# MercurialSDR_PWR.net
KiCad netlist of a schematic drawn in Altium Designer
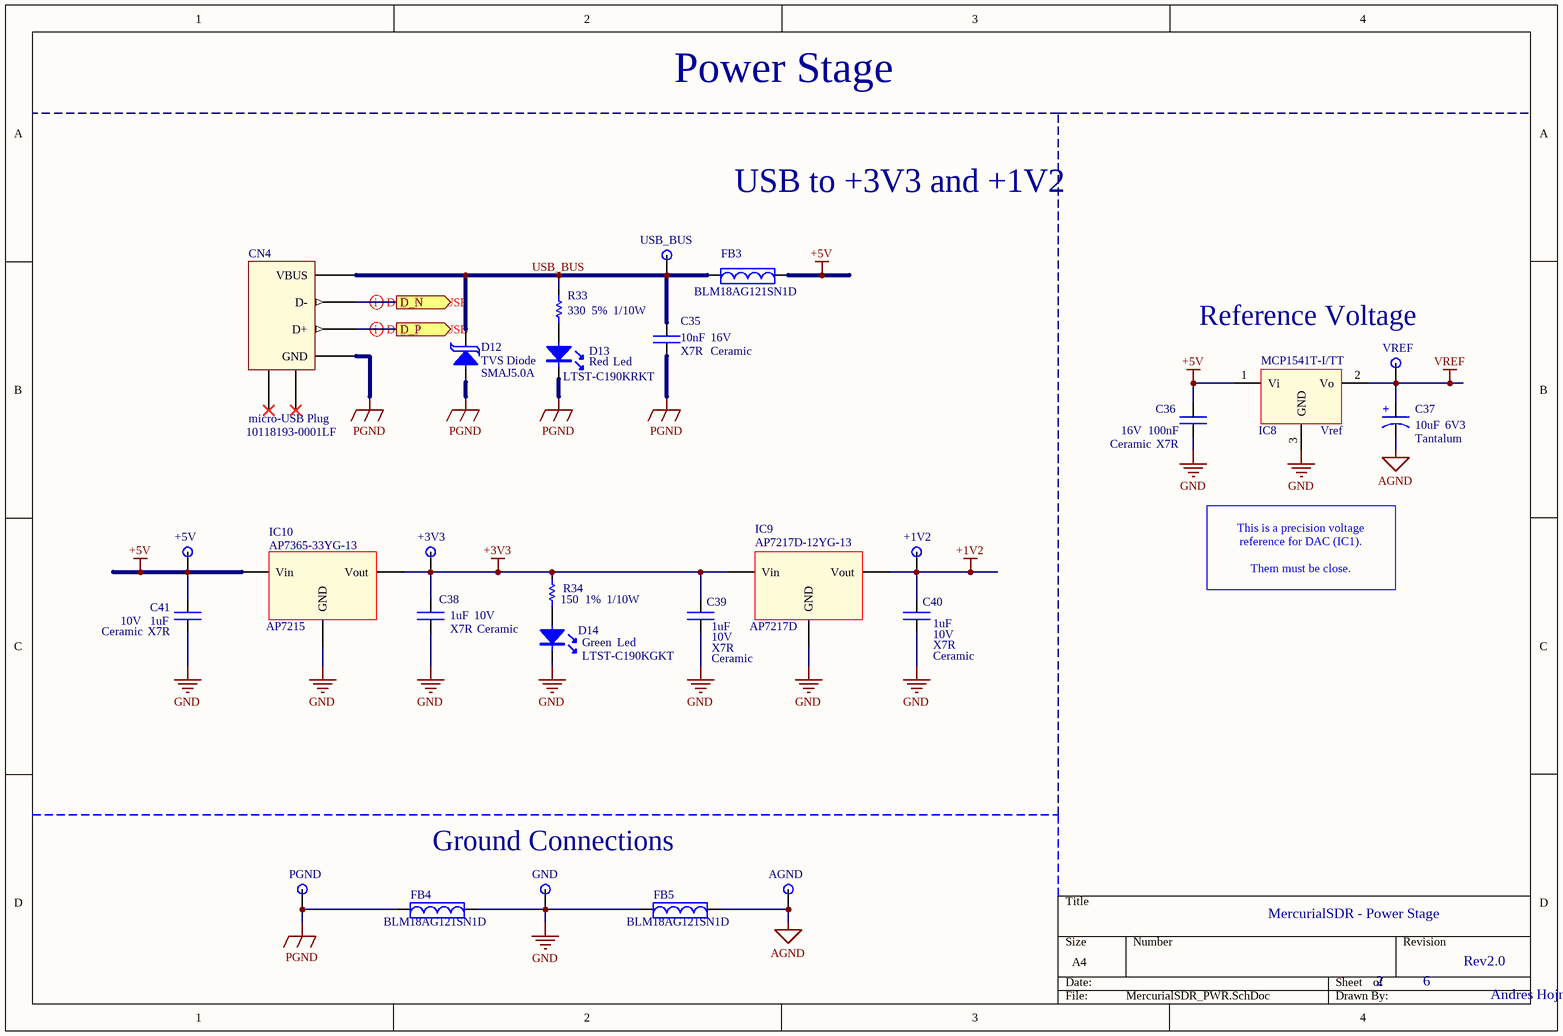
[diagram p0: MercurialSDR_PWR.SchDoc]

(export (version "E")
  (design (tool "Eeschema 10.0.6"))
  (components
    (comp (ref "C35")
      (value "10nF")
      (footprint "CAP_0603")
      (description "Capacitor no polarizado")
      (fields
        (field (name "TEMP COEF") "X7R")
        (field (name "PART NUMBER") "CC0603KRX7R7BB103")
        (field (name "VR") "16V")
        (field (name "MATERIAL") "Ceramic")
        (field (name "Comment") "Capacitor")
      )
      (libsource (lib "MercurialSDR") (part "Cap"))
    )
    (comp (ref "C36")
      (value "100nF")
      (footprint "CAP_0603")
      (description "Capacitor no polarizado")
      (fields
        (field (name "TEMP COEF") "X7R")
        (field (name "PART NUMBER") "CL10B104KO8NNNC")
        (field (name "VR") "16V")
        (field (name "MATERIAL") "Ceramic")
        (field (name "Comment") "Capacitor")
      )
      (libsource (lib "MercurialSDR") (part "Cap"))
    )
    (comp (ref "C37")
      (value "10uF")
      (footprint "CAP_TANT_1206")
      (description "Capacitor polarizado")
      (fields
        (field (name "PART NUMBER") "TAJA106K006RNJ")
        (field (name "VR") "6V3")
        (field (name "MATERIAL") "Tantalum")
        (field (name "Comment") "Capacitor Polarizado")
      )
      (libsource (lib "MercurialSDR") (part "Cap Pol"))
    )
    (comp (ref "C38")
      (value "1uF")
      (footprint "CAP_0603")
      (description "Capacitor no polarizado")
      (fields
        (field (name "TEMP COEF") "X7R")
        (field (name "PART NUMBER") "CL10B105KP8NNNC")
        (field (name "VR") "10V")
        (field (name "MATERIAL") "Ceramic")
        (field (name "Comment") "Capacitor")
      )
      (libsource (lib "MercurialSDR") (part "Cap"))
    )
    (comp (ref "C39")
      (value "1uF")
      (footprint "CAP_0603")
      (description "Capacitor no polarizado")
      (fields
        (field (name "TEMP COEF") "X7R")
        (field (name "PART NUMBER") "CL10B105KP8NNNC")
        (field (name "VR") "10V")
        (field (name "MATERIAL") "Ceramic")
        (field (name "Comment") "Capacitor")
      )
      (libsource (lib "MercurialSDR") (part "Cap"))
    )
    (comp (ref "C40")
      (value "1uF")
      (footprint "CAP_0603")
      (description "Capacitor no polarizado")
      (fields
        (field (name "TEMP COEF") "X7R")
        (field (name "PART NUMBER") "CL10B105KP8NNNC")
        (field (name "VR") "10V")
        (field (name "MATERIAL") "Ceramic")
        (field (name "Comment") "Capacitor")
      )
      (libsource (lib "MercurialSDR") (part "Cap"))
    )
    (comp (ref "C41")
      (value "1uF")
      (footprint "CAP_0603")
      (description "Capacitor no polarizado")
      (fields
        (field (name "TEMP COEF") "X7R")
        (field (name "PART NUMBER") "CL10B105KP8NNNC")
        (field (name "VR") "10V")
        (field (name "MATERIAL") "Ceramic")
        (field (name "Comment") "Capacitor")
      )
      (libsource (lib "MercurialSDR") (part "Cap"))
    )
    (comp (ref "CN4")
      (value "micro-USB Plug")
      (footprint "USB_Micro")
      (description "USB Plug")
      (fields (field (name "PART NUMBER") "10118193-0001LF"))
      (libsource (lib "MercurialSDR") (part "USB Plug"))
    )
    (comp (ref "D12")
      (value "TVS Diode")
      (footprint "DO-214AC")
      (description "TVS (Supresor de transitorios)")
      (fields (field (name "PART NUMBER") "SMAJ5.0A"))
      (libsource (lib "MercurialSDR") (part "TVS_DIODE"))
    )
    (comp (ref "D13")
      (value "Led")
      (footprint "LED_0603")
      (fields (field (name "COLOR") "Red") (field (name "PART NUMBER") "LTST-C190KRKT"))
      (libsource (lib "MercurialSDR") (part "Led"))
    )
    (comp (ref "D14")
      (value "Led")
      (footprint "LED_0603")
      (fields (field (name "COLOR") "Green") (field (name "PART NUMBER") "LTST-C190KGKT"))
      (libsource (lib "MercurialSDR") (part "Led"))
    )
    (comp (ref "FB3")
      (value "Ferrite Bead")
      (footprint "FERRITE_BEAD_0603")
      (fields (field (name "PART NUMBER") "BLM18AG121SN1D"))
      (libsource (lib "MercurialSDR") (part "Ferrite Bead"))
    )
    (comp (ref "FB4")
      (value "Ferrite Bead")
      (footprint "FERRITE_BEAD_0603")
      (fields (field (name "PART NUMBER") "BLM18AG121SN1D"))
      (libsource (lib "MercurialSDR") (part "Ferrite Bead"))
    )
    (comp (ref "FB5")
      (value "Ferrite Bead")
      (footprint "FERRITE_BEAD_0603")
      (fields (field (name "PART NUMBER") "BLM18AG121SN1D"))
      (libsource (lib "MercurialSDR") (part "Ferrite Bead"))
    )
    (comp (ref "IC8")
      (value "Vref")
      (footprint "SOT-23-3")
      (description "Reference Voltage")
      (fields (field (name "PART NUMBER") "MCP1541T-I/TT"))
      (libsource (lib "MercurialSDR") (part "MCP1541"))
    )
    (comp (ref "IC9")
      (value "AP7217D")
      (footprint "SOT89-3L")
      (description "Linear Voltage Regulator 1V2")
      (fields (field (name "PART NUMBER") "AP7217D-12YG-13"))
      (libsource (lib "MercurialSDR") (part "AP7217D"))
    )
    (comp (ref "IC10")
      (value "AP7215")
      (footprint "SOT89-3L")
      (description "Linear Voltage Regulator 3v3")
      (fields (field (name "PART NUMBER") "AP7365-33YG-13"))
      (libsource (lib "MercurialSDR") (part "AP7215"))
    )
    (comp (ref "R33")
      (value "330")
      (footprint "RES_0603")
      (description "Resistor")
      (fields
        (field (name "POWER") "1/10W")
        (field (name "PART NUMBER") "CR0603-JW-331ELF")
        (field (name "TOLERANCE") "5%")
        (field (name "Comment") "Resistor SMD")
      )
      (libsource (lib "MercurialSDR") (part "Res"))
    )
    (comp (ref "R34")
      (value "150")
      (footprint "RES_0603")
      (description "Resistor")
      (fields
        (field (name "POWER") "1/10W")
        (field (name "PART NUMBER") "ERJ-3EKF1500V")
        (field (name "TOLERANCE") "1%")
        (field (name "Comment") "Resistor SMD")
      )
      (libsource (lib "MercurialSDR") (part "Res"))
    )
    (comp (ref "TP9")
      (value "Test Point")
      (footprint "TP_TOP")
      (fields (field (name "TP NAME") "USB_BUS"))
      (libsource (lib "MercurialSDR") (part "Test Point"))
    )
    (comp (ref "TP10")
      (value "Test Point")
      (footprint "TP_TOP")
      (fields (field (name "TP NAME") "VREF"))
      (libsource (lib "MercurialSDR") (part "Test Point"))
    )
    (comp (ref "TP11")
      (value "Test Point")
      (footprint "TP_TOP")
      (fields (field (name "TP NAME") "+5V"))
      (libsource (lib "MercurialSDR") (part "Test Point"))
    )
    (comp (ref "TP12")
      (value "Test Point")
      (footprint "TP_TOP")
      (fields (field (name "TP NAME") "+3V3"))
      (libsource (lib "MercurialSDR") (part "Test Point"))
    )
    (comp (ref "TP13")
      (value "Test Point")
      (footprint "TP_TOP")
      (fields (field (name "TP NAME") "+1V2"))
      (libsource (lib "MercurialSDR") (part "Test Point"))
    )
    (comp (ref "TP14")
      (value "Test Point")
      (footprint "TP_TH")
      (fields (field (name "TP NAME") "PGND"))
      (libsource (lib "MercurialSDR") (part "Test Point"))
    )
    (comp (ref "TP15")
      (value "Test Point")
      (footprint "TP_TOP")
      (fields (field (name "TP NAME") "GND"))
      (libsource (lib "MercurialSDR") (part "Test Point"))
    )
    (comp (ref "TP16")
      (value "Test Point")
      (footprint "TP_TOP")
      (fields (field (name "TP NAME") "AGND"))
      (libsource (lib "MercurialSDR") (part "Test Point"))
    )
  )
  (nets
    (net (code "1") (name "+1V2") (class "Default")
      (node (ref "C40") (pin "1") (pinfunction "1_1") (pintype "passive"))
      (node (ref "IC9") (pin "3") (pinfunction "Vout_3") (pintype "passive"))
      (node (ref "TP13") (pin "1") (pinfunction "TP?_1") (pintype "passive"))
    )
    (net (code "2") (name "+3V3") (class "Default")
      (node (ref "C38") (pin "1") (pinfunction "1_1") (pintype "passive"))
      (node (ref "C39") (pin "1") (pinfunction "1_1") (pintype "passive"))
      (node (ref "IC10") (pin "1") (pinfunction "Vout_1") (pintype "passive"))
      (node (ref "IC9") (pin "2") (pinfunction "Vin_2") (pintype "passive"))
      (node (ref "R34") (pin "1") (pinfunction "1_1") (pintype "passive"))
      (node (ref "TP12") (pin "1") (pinfunction "TP?_1") (pintype "passive"))
    )
    (net (code "3") (name "+5V") (class "Default")
      (node (ref "C36") (pin "1") (pinfunction "1_1") (pintype "passive"))
      (node (ref "C41") (pin "1") (pinfunction "1_1") (pintype "passive"))
      (node (ref "FB3") (pin "2") (pinfunction "2_2") (pintype "passive"))
      (node (ref "IC10") (pin "3") (pinfunction "Vin_3") (pintype "passive"))
      (node (ref "IC8") (pin "1") (pinfunction "Vi_1") (pintype "passive"))
      (node (ref "TP11") (pin "1") (pinfunction "TP?_1") (pintype "passive"))
    )
    (net (code "4") (name "/D_N") (class "Default")
      (node (ref "CN4") (pin "2") (pinfunction "D-_2") (pintype "output"))
    )
    (net (code "5") (name "/D_P") (class "Default")
      (node (ref "CN4") (pin "3") (pinfunction "D+_3") (pintype "output"))
    )
    (net (code "6") (name "/USB_BUS") (class "Default")
      (node (ref "C35") (pin "1") (pinfunction "1_1") (pintype "passive"))
      (node (ref "CN4") (pin "1") (pinfunction "VBUS_1") (pintype "power_in"))
      (node (ref "D12") (pin "2") (pinfunction "K_2") (pintype "passive"))
      (node (ref "FB3") (pin "1") (pinfunction "1_1") (pintype "passive"))
      (node (ref "R33") (pin "1") (pinfunction "1_1") (pintype "passive"))
      (node (ref "TP9") (pin "1") (pinfunction "TP?_1") (pintype "passive"))
    )
    (net (code "7") (name "AGND") (class "Default")
      (node (ref "C37") (pin "2") (pinfunction "2_2") (pintype "passive"))
      (node (ref "FB5") (pin "2") (pinfunction "2_2") (pintype "passive"))
      (node (ref "TP16") (pin "1") (pinfunction "TP?_1") (pintype "passive"))
    )
    (net (code "8") (name "GND") (class "Default")
      (node (ref "C36") (pin "2") (pinfunction "2_2") (pintype "passive"))
      (node (ref "C38") (pin "2") (pinfunction "2_2") (pintype "passive"))
      (node (ref "C39") (pin "2") (pinfunction "2_2") (pintype "passive"))
      (node (ref "C40") (pin "2") (pinfunction "2_2") (pintype "passive"))
      (node (ref "C41") (pin "2") (pinfunction "2_2") (pintype "passive"))
      (node (ref "D14") (pin "2") (pinfunction "K_2") (pintype "passive"))
      (node (ref "FB4") (pin "2") (pinfunction "2_2") (pintype "passive"))
      (node (ref "FB5") (pin "1") (pinfunction "1_1") (pintype "passive"))
      (node (ref "IC10") (pin "2") (pinfunction "GND_2") (pintype "passive"))
      (node (ref "IC8") (pin "3") (pinfunction "GND_3") (pintype "passive"))
      (node (ref "IC9") (pin "1") (pinfunction "GND_1") (pintype "passive"))
      (node (ref "TP15") (pin "1") (pinfunction "TP?_1") (pintype "passive"))
    )
    (net (code "9") (name "Net-(D13-A)") (class "Default")
      (node (ref "D13") (pin "1") (pinfunction "A_1") (pintype "passive"))
      (node (ref "R33") (pin "2") (pinfunction "2_2") (pintype "passive"))
    )
    (net (code "10") (name "Net-(D14-A)") (class "Default")
      (node (ref "D14") (pin "1") (pinfunction "A_1") (pintype "passive"))
      (node (ref "R34") (pin "2") (pinfunction "2_2") (pintype "passive"))
    )
    (net (code "11") (name "PGND") (class "Default")
      (node (ref "C35") (pin "2") (pinfunction "2_2") (pintype "passive"))
      (node (ref "CN4") (pin "4") (pinfunction "GND_4") (pintype "power_in"))
      (node (ref "D12") (pin "1") (pinfunction "A_1") (pintype "passive"))
      (node (ref "D13") (pin "2") (pinfunction "K_2") (pintype "passive"))
      (node (ref "FB4") (pin "1") (pinfunction "1_1") (pintype "passive"))
      (node (ref "TP14") (pin "1") (pinfunction "TP?_1") (pintype "passive"))
    )
    (net (code "12") (name "VREF") (class "Default")
      (node (ref "C37") (pin "1") (pinfunction "1_1") (pintype "passive"))
      (node (ref "IC8") (pin "2") (pinfunction "Vo_2") (pintype "passive"))
      (node (ref "TP10") (pin "1") (pinfunction "TP?_1") (pintype "passive"))
    )
    (net (code "13") (name "unconnected-(CN4-Shield-Pad5)") (class "Default")
      (node (ref "CN4") (pin "5") (pinfunction "Shield_5") (pintype "passive+no_connect"))
    )
    (net (code "14") (name "unconnected-(CN4-Shield-Pad6)") (class "Default")
      (node (ref "CN4") (pin "6") (pinfunction "Shield_6") (pintype "passive+no_connect"))
    )
  )
)
